# Schematic.net
KiCad netlist of a schematic drawn in Altium Designer
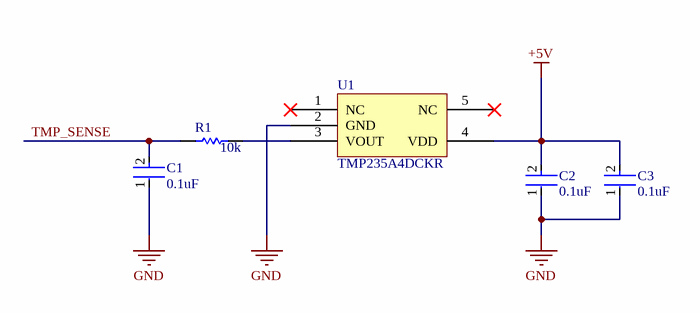
[diagram p0: Schematic.SchDoc]

(export (version "E")
  (design (tool "Eeschema 10.0.6"))
  (components
    (comp (ref "C1")
      (value "TMK105BJ104KV-F")
      (footprint "CAPC1005X55N")
      (description "0.1 µF ±10% 25V Ceramic Capacitor X5R 0402 (1005 Metric)")
      (fields (field (name "CAPACITANCE") "0.1uF"))
      (libsource (lib "zCCM_SchLib") (part "TMK105BJ104KV-F"))
    )
    (comp (ref "C2")
      (value "TMK105BJ104KV-F")
      (footprint "CAPC1005X55N")
      (description "0.1 µF ±10% 25V Ceramic Capacitor X5R 0402 (1005 Metric)")
      (fields (field (name "CAPACITANCE") "0.1uF"))
      (libsource (lib "zCCM_SchLib") (part "TMK105BJ104KV-F"))
    )
    (comp (ref "C3")
      (value "0.1uF")
      (footprint "CAPC1005X55N")
      (description "0.1 µF ±10% 25V Ceramic Capacitor X5R 0402 (1005 Metric)")
      (fields (field (name "PARTNUM") "TMK105BJ104KV-F"))
      (libsource (lib "SCHLIB") (part "TMK105BJ104KV-F"))
    )
    (comp (ref "R1")
      (value "RC0402JR-0710KL")
      (footprint "R0402")
      (description "10 kOhms ±5% 0.063W, 1/16W Chip Resistor 0402 (1005 Metric) Moisture Resistant Thick Film")
      (fields (field (name "RESISTANCE") "10k"))
      (libsource (lib "zCCM_SchLib") (part "RC0402JR-0710KL"))
    )
    (comp (ref "U1")
      (value "TMP235A4DCKR")
      (footprint "TMP")
      (description "Temperature Sensor Analog, Local -40°C ~ 150°C 10mV/°C SC-70-5")
      (libsource (lib "zCCM_SchLib") (part "TMP235A4DCKR"))
    )
  )
  (nets
    (net (code "1") (name "+5V") (class "Default")
      (node (ref "C2") (pin "2") (pinfunction "2_2") (pintype "passive"))
      (node (ref "C3") (pin "2") (pinfunction "2_2") (pintype "passive"))
      (node (ref "U1") (pin "4") (pinfunction "VDD_4") (pintype "passive"))
    )
    (net (code "2") (name "/TMP_SENSE") (class "Default")
      (node (ref "C1") (pin "2") (pinfunction "2_2") (pintype "passive"))
      (node (ref "R1") (pin "2") (pinfunction "2_2") (pintype "passive"))
    )
    (net (code "3") (name "GND") (class "Default")
      (node (ref "C1") (pin "1") (pinfunction "1_1") (pintype "passive"))
      (node (ref "C2") (pin "1") (pinfunction "1_1") (pintype "passive"))
      (node (ref "C3") (pin "1") (pinfunction "1_1") (pintype "passive"))
      (node (ref "U1") (pin "2") (pinfunction "GND_2") (pintype "passive"))
    )
    (net (code "4") (name "Net-(U1-VOUT)") (class "Default")
      (node (ref "R1") (pin "1") (pinfunction "1_1") (pintype "passive"))
      (node (ref "U1") (pin "3") (pinfunction "VOUT_3") (pintype "passive"))
    )
    (net (code "5") (name "unconnected-(U1-NC-Pad1)") (class "Default")
      (node (ref "U1") (pin "1") (pinfunction "NC_1") (pintype "passive+no_connect"))
    )
    (net (code "6") (name "unconnected-(U1-NC-Pad5)") (class "Default")
      (node (ref "U1") (pin "5") (pinfunction "NC_5") (pintype "passive+no_connect"))
    )
  )
)
